# satshakit_power_board.net
KiCad netlist of a schematic drawn in EAGLE
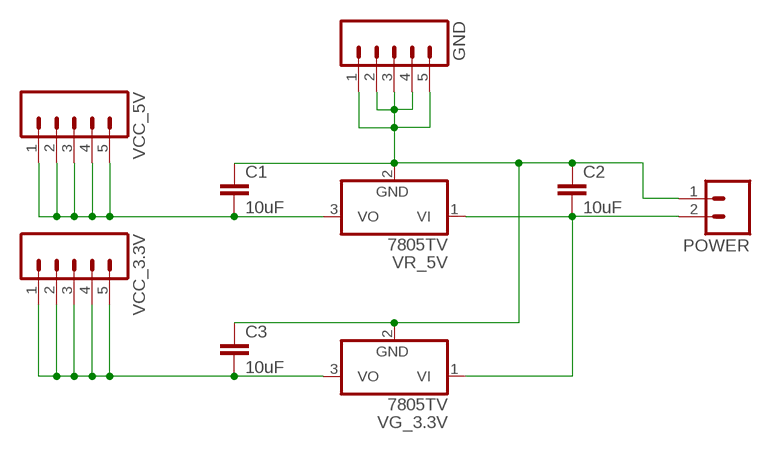
[diagram p0: schematic, sheet 1]

(export (version "E")
  (design (tool "Eeschema 10.0.6"))
  (components
    (comp (ref "C1")
      (value "10uF")
      (footprint "eagle-import:1206")
      (libsource (lib "eagle-import") (part "CAP1206"))
    )
    (comp (ref "C2")
      (value "10uF")
      (footprint "eagle-import:1206")
      (libsource (lib "eagle-import") (part "CAP1206"))
    )
    (comp (ref "C3")
      (value "10uF")
      (footprint "eagle-import:1206")
      (libsource (lib "eagle-import") (part "CAP1206"))
    )
    (comp (ref "GND")
      (value "M05PTH_LONGPADS")
      (footprint "eagle-import:1X05_LONGPADS")
      (libsource (lib "eagle-import") (part "M05PTH_LONGPADS"))
    )
    (comp (ref "POWER")
      (value "M02")
      (footprint "eagle-import:1X02_LONGPADS")
      (libsource (lib "eagle-import") (part "M02"))
    )
    (comp (ref "VCC_3.3V")
      (value "M05PTH_LONGPADS")
      (footprint "eagle-import:1X05_LONGPADS")
      (libsource (lib "eagle-import") (part "M05PTH_LONGPADS"))
    )
    (comp (ref "VCC_5V")
      (value "M05PTH_LONGPADS")
      (footprint "eagle-import:1X05_LONGPADS")
      (libsource (lib "eagle-import") (part "M05PTH_LONGPADS"))
    )
    (comp (ref "VG_3.3V")
      (value "7805TV")
      (footprint "eagle-import:TO220V")
      (libsource (lib "eagle-import") (part "78TV05"))
    )
    (comp (ref "VR_5V")
      (value "7805TV")
      (footprint "eagle-import:TO220V")
      (libsource (lib "eagle-import") (part "78TV05"))
    )
  )
  (nets
    (net (code "1") (name "Net-(VG_3.3V-GND)") (class "Default")
      (node (ref "C1") (pin "1") (pinfunction "1_1") (pintype "passive"))
      (node (ref "C2") (pin "1") (pinfunction "1_1") (pintype "passive"))
      (node (ref "C3") (pin "1") (pinfunction "1_1") (pintype "passive"))
      (node (ref "GND") (pin "1") (pinfunction "1_1") (pintype "passive"))
      (node (ref "GND") (pin "2") (pinfunction "2_2") (pintype "passive"))
      (node (ref "GND") (pin "3") (pinfunction "3_3") (pintype "passive"))
      (node (ref "GND") (pin "4") (pinfunction "4_4") (pintype "passive"))
      (node (ref "GND") (pin "5") (pinfunction "5_5") (pintype "passive"))
      (node (ref "POWER") (pin "1") (pinfunction "1_1") (pintype "passive"))
      (node (ref "VG_3.3V") (pin "2") (pinfunction "GND_2") (pintype "passive"))
      (node (ref "VR_5V") (pin "2") (pinfunction "GND_2") (pintype "passive"))
    )
    (net (code "2") (name "Net-(VG_3.3V-VI)") (class "Default")
      (node (ref "C2") (pin "2") (pinfunction "2_2") (pintype "passive"))
      (node (ref "POWER") (pin "2") (pinfunction "2_2") (pintype "passive"))
      (node (ref "VG_3.3V") (pin "1") (pinfunction "VI_1") (pintype "input"))
      (node (ref "VR_5V") (pin "1") (pinfunction "VI_1") (pintype "input"))
    )
    (net (code "3") (name "Net-(VG_3.3V-VO)") (class "Default")
      (node (ref "C3") (pin "2") (pinfunction "2_2") (pintype "passive"))
      (node (ref "VCC_3.3V") (pin "1") (pinfunction "1_1") (pintype "passive"))
      (node (ref "VCC_3.3V") (pin "2") (pinfunction "2_2") (pintype "passive"))
      (node (ref "VCC_3.3V") (pin "3") (pinfunction "3_3") (pintype "passive"))
      (node (ref "VCC_3.3V") (pin "4") (pinfunction "4_4") (pintype "passive"))
      (node (ref "VCC_3.3V") (pin "5") (pinfunction "5_5") (pintype "passive"))
      (node (ref "VG_3.3V") (pin "3") (pinfunction "VO_3") (pintype "passive"))
    )
    (net (code "4") (name "Net-(VR_5V-VO)") (class "Default")
      (node (ref "C1") (pin "2") (pinfunction "2_2") (pintype "passive"))
      (node (ref "VCC_5V") (pin "1") (pinfunction "1_1") (pintype "passive"))
      (node (ref "VCC_5V") (pin "2") (pinfunction "2_2") (pintype "passive"))
      (node (ref "VCC_5V") (pin "3") (pinfunction "3_3") (pintype "passive"))
      (node (ref "VCC_5V") (pin "4") (pinfunction "4_4") (pintype "passive"))
      (node (ref "VCC_5V") (pin "5") (pinfunction "5_5") (pintype "passive"))
      (node (ref "VR_5V") (pin "3") (pinfunction "VO_3") (pintype "passive"))
    )
  )
)
